# QWICCFeather_001.net
KiCad netlist of a schematic drawn in EAGLE
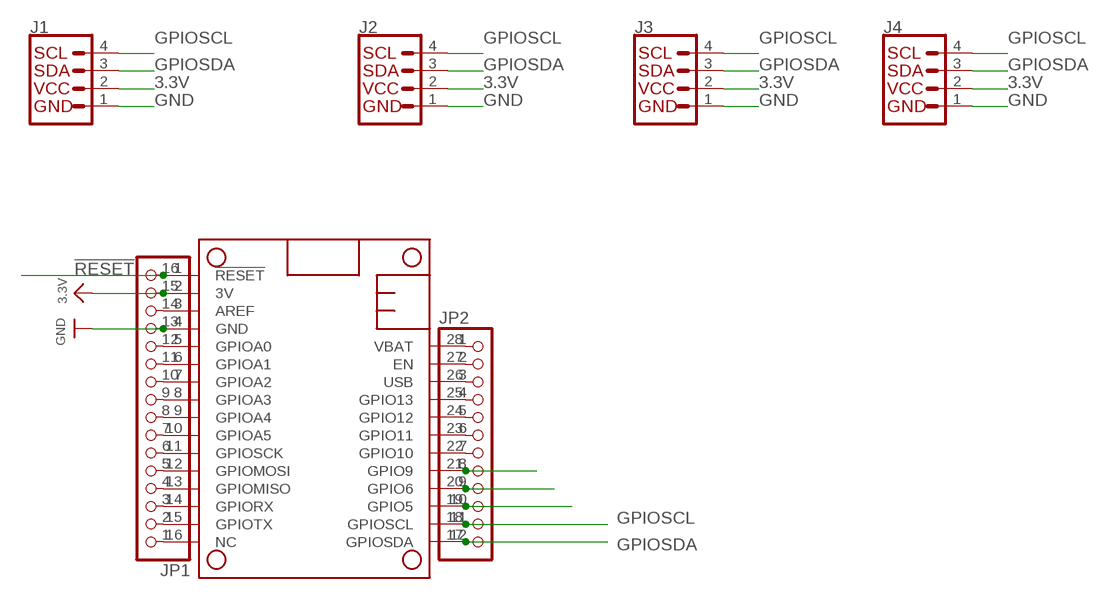
[diagram p0: schematic, sheet 1]

(export (version "E")
  (design (tool "Eeschema 10.0.6"))
  (components
    (comp (ref "J1")
      (value "QWIIC_CONNECTORJS-1MM")
      (footprint "eagle-import:1X04_1MM_RA")
      (libsource (lib "eagle-import") (part "QWIIC_CONNECTORJS-1MM"))
    )
    (comp (ref "J2")
      (value "QWIIC_CONNECTORJS-1MM")
      (footprint "eagle-import:1X04_1MM_RA")
      (libsource (lib "eagle-import") (part "QWIIC_CONNECTORJS-1MM"))
    )
    (comp (ref "J3")
      (value "QWIIC_CONNECTORJS-1MM")
      (footprint "eagle-import:1X04_1MM_RA")
      (libsource (lib "eagle-import") (part "QWIIC_CONNECTORJS-1MM"))
    )
    (comp (ref "J4")
      (value "QWIIC_CONNECTORJS-1MM")
      (footprint "eagle-import:1X04_1MM_RA")
      (libsource (lib "eagle-import") (part "QWIIC_CONNECTORJS-1MM"))
    )
    (comp (ref "JP1")
      (value "HEADER-1X16ROUND")
      (footprint "eagle-import:1X16_ROUND")
      (libsource (lib "eagle-import") (part "HEADER-1X16ROUND"))
    )
    (comp (ref "JP2")
      (value "HEADER-1X12")
      (footprint "eagle-import:1X12_ROUND")
      (libsource (lib "eagle-import") (part "HEADER-1X12"))
    )
    (comp (ref "MS1")
      (value "FEATHERWING")
      (footprint "eagle-import:FEATHERWING")
      (libsource (lib "eagle-import") (part "FEATHERWING"))
    )
  )
  (nets
    (net (code "1") (name "/GPIOSCL") (class "Default")
      (node (ref "J1") (pin "4") (pinfunction "SCL_4") (pintype "passive"))
      (node (ref "J2") (pin "4") (pinfunction "SCL_4") (pintype "passive"))
      (node (ref "J3") (pin "4") (pinfunction "SCL_4") (pintype "passive"))
      (node (ref "J4") (pin "4") (pinfunction "SCL_4") (pintype "passive"))
      (node (ref "JP2") (pin "11") (pinfunction "11_11") (pintype "passive"))
      (node (ref "MS1") (pin "18") (pinfunction "GPIOSCL_18") (pintype "bidirectional"))
    )
    (net (code "2") (name "/GPIOSDA") (class "Default")
      (node (ref "J1") (pin "3") (pinfunction "SDA_3") (pintype "passive"))
      (node (ref "J2") (pin "3") (pinfunction "SDA_3") (pintype "passive"))
      (node (ref "J3") (pin "3") (pinfunction "SDA_3") (pintype "passive"))
      (node (ref "J4") (pin "3") (pinfunction "SDA_3") (pintype "passive"))
      (node (ref "JP2") (pin "12") (pinfunction "12_12") (pintype "passive"))
      (node (ref "MS1") (pin "17") (pinfunction "GPIOSDA_17") (pintype "bidirectional"))
    )
    (net (code "3") (name "/~{RESET}") (class "Default")
      (node (ref "JP1") (pin "16") (pinfunction "16_16") (pintype "passive"))
      (node (ref "MS1") (pin "1") (pinfunction "~{RESET}_1") (pintype "input"))
    )
    (net (code "4") (name "3.3V") (class "Default")
      (node (ref "J1") (pin "2") (pinfunction "VCC_2") (pintype "power_in"))
      (node (ref "J2") (pin "2") (pinfunction "VCC_2") (pintype "power_in"))
      (node (ref "J3") (pin "2") (pinfunction "VCC_2") (pintype "power_in"))
      (node (ref "J4") (pin "2") (pinfunction "VCC_2") (pintype "power_in"))
      (node (ref "JP1") (pin "15") (pinfunction "15_15") (pintype "passive"))
      (node (ref "MS1") (pin "2") (pinfunction "3V_2") (pintype "power_in"))
    )
    (net (code "5") (name "GND") (class "Default")
      (node (ref "J1") (pin "1") (pinfunction "GND_1") (pintype "power_in"))
      (node (ref "J2") (pin "1") (pinfunction "GND_1") (pintype "power_in"))
      (node (ref "J3") (pin "1") (pinfunction "GND_1") (pintype "power_in"))
      (node (ref "J4") (pin "1") (pinfunction "GND_1") (pintype "power_in"))
      (node (ref "JP1") (pin "13") (pinfunction "13_13") (pintype "passive"))
      (node (ref "MS1") (pin "4") (pinfunction "GND_4") (pintype "power_in"))
    )
    (net (code "6") (name "Net-(MS1-AREF)") (class "Default")
      (node (ref "JP1") (pin "14") (pinfunction "14_14") (pintype "passive"))
      (node (ref "MS1") (pin "3") (pinfunction "AREF_3") (pintype "passive"))
    )
    (net (code "7") (name "Net-(MS1-EN)") (class "Default")
      (node (ref "JP2") (pin "2") (pinfunction "2_2") (pintype "passive"))
      (node (ref "MS1") (pin "27") (pinfunction "EN_27") (pintype "passive"))
    )
    (net (code "8") (name "Net-(MS1-GPIO5)") (class "Default")
      (node (ref "JP2") (pin "10") (pinfunction "10_10") (pintype "passive"))
      (node (ref "MS1") (pin "19") (pinfunction "GPIO5_19") (pintype "bidirectional"))
    )
    (net (code "9") (name "Net-(MS1-GPIO6)") (class "Default")
      (node (ref "JP2") (pin "9") (pinfunction "9_9") (pintype "passive"))
      (node (ref "MS1") (pin "20") (pinfunction "GPIO6_20") (pintype "bidirectional"))
    )
    (net (code "10") (name "Net-(MS1-GPIO9)") (class "Default")
      (node (ref "JP2") (pin "8") (pinfunction "8_8") (pintype "passive"))
      (node (ref "MS1") (pin "21") (pinfunction "GPIO9_21") (pintype "bidirectional"))
    )
    (net (code "11") (name "Net-(MS1-GPIO10)") (class "Default")
      (node (ref "JP2") (pin "7") (pinfunction "7_7") (pintype "passive"))
      (node (ref "MS1") (pin "22") (pinfunction "GPIO10_22") (pintype "bidirectional"))
    )
    (net (code "12") (name "Net-(MS1-GPIO11)") (class "Default")
      (node (ref "JP2") (pin "6") (pinfunction "6_6") (pintype "passive"))
      (node (ref "MS1") (pin "23") (pinfunction "GPIO11_23") (pintype "bidirectional"))
    )
    (net (code "13") (name "Net-(MS1-GPIO12)") (class "Default")
      (node (ref "JP2") (pin "5") (pinfunction "5_5") (pintype "passive"))
      (node (ref "MS1") (pin "24") (pinfunction "GPIO12_24") (pintype "bidirectional"))
    )
    (net (code "14") (name "Net-(MS1-GPIO13)") (class "Default")
      (node (ref "JP2") (pin "4") (pinfunction "4_4") (pintype "passive"))
      (node (ref "MS1") (pin "25") (pinfunction "GPIO13_25") (pintype "bidirectional"))
    )
    (net (code "15") (name "Net-(MS1-GPIOA0)") (class "Default")
      (node (ref "JP1") (pin "12") (pinfunction "12_12") (pintype "passive"))
      (node (ref "MS1") (pin "5") (pinfunction "GPIOA0_5") (pintype "bidirectional"))
    )
    (net (code "16") (name "Net-(MS1-GPIOA1)") (class "Default")
      (node (ref "JP1") (pin "11") (pinfunction "11_11") (pintype "passive"))
      (node (ref "MS1") (pin "6") (pinfunction "GPIOA1_6") (pintype "bidirectional"))
    )
    (net (code "17") (name "Net-(MS1-GPIOA2)") (class "Default")
      (node (ref "JP1") (pin "10") (pinfunction "10_10") (pintype "passive"))
      (node (ref "MS1") (pin "7") (pinfunction "GPIOA2_7") (pintype "bidirectional"))
    )
    (net (code "18") (name "Net-(MS1-GPIOA3)") (class "Default")
      (node (ref "JP1") (pin "9") (pinfunction "9_9") (pintype "passive"))
      (node (ref "MS1") (pin "8") (pinfunction "GPIOA3_8") (pintype "bidirectional"))
    )
    (net (code "19") (name "Net-(MS1-GPIOA4)") (class "Default")
      (node (ref "JP1") (pin "8") (pinfunction "8_8") (pintype "passive"))
      (node (ref "MS1") (pin "9") (pinfunction "GPIOA4_9") (pintype "bidirectional"))
    )
    (net (code "20") (name "Net-(MS1-GPIOA5)") (class "Default")
      (node (ref "JP1") (pin "7") (pinfunction "7_7") (pintype "passive"))
      (node (ref "MS1") (pin "10") (pinfunction "GPIOA5_10") (pintype "bidirectional"))
    )
    (net (code "21") (name "Net-(MS1-GPIOMISO)") (class "Default")
      (node (ref "JP1") (pin "4") (pinfunction "4_4") (pintype "passive"))
      (node (ref "MS1") (pin "13") (pinfunction "GPIOMISO_13") (pintype "bidirectional"))
    )
    (net (code "22") (name "Net-(MS1-GPIOMOSI)") (class "Default")
      (node (ref "JP1") (pin "5") (pinfunction "5_5") (pintype "passive"))
      (node (ref "MS1") (pin "12") (pinfunction "GPIOMOSI_12") (pintype "bidirectional"))
    )
    (net (code "23") (name "Net-(MS1-GPIORX)") (class "Default")
      (node (ref "JP1") (pin "3") (pinfunction "3_3") (pintype "passive"))
      (node (ref "MS1") (pin "14") (pinfunction "GPIORX_14") (pintype "bidirectional"))
    )
    (net (code "24") (name "Net-(MS1-GPIOSCK)") (class "Default")
      (node (ref "JP1") (pin "6") (pinfunction "6_6") (pintype "passive"))
      (node (ref "MS1") (pin "11") (pinfunction "GPIOSCK_11") (pintype "bidirectional"))
    )
    (net (code "25") (name "Net-(MS1-GPIOTX)") (class "Default")
      (node (ref "JP1") (pin "2") (pinfunction "2_2") (pintype "passive"))
      (node (ref "MS1") (pin "15") (pinfunction "GPIOTX_15") (pintype "bidirectional"))
    )
    (net (code "26") (name "Net-(MS1-NC)") (class "Default")
      (node (ref "JP1") (pin "1") (pinfunction "1_1") (pintype "passive"))
      (node (ref "MS1") (pin "16") (pinfunction "NC_16") (pintype "passive"))
    )
    (net (code "27") (name "Net-(MS1-USB)") (class "Default")
      (node (ref "JP2") (pin "3") (pinfunction "3_3") (pintype "passive"))
      (node (ref "MS1") (pin "26") (pinfunction "USB_26") (pintype "power_in"))
    )
    (net (code "28") (name "Net-(MS1-VBAT)") (class "Default")
      (node (ref "JP2") (pin "1") (pinfunction "1_1") (pintype "passive"))
      (node (ref "MS1") (pin "28") (pinfunction "VBAT_28") (pintype "power_in"))
    )
  )
)
